# MCU.net
KiCad netlist of a schematic drawn in Altium Designer
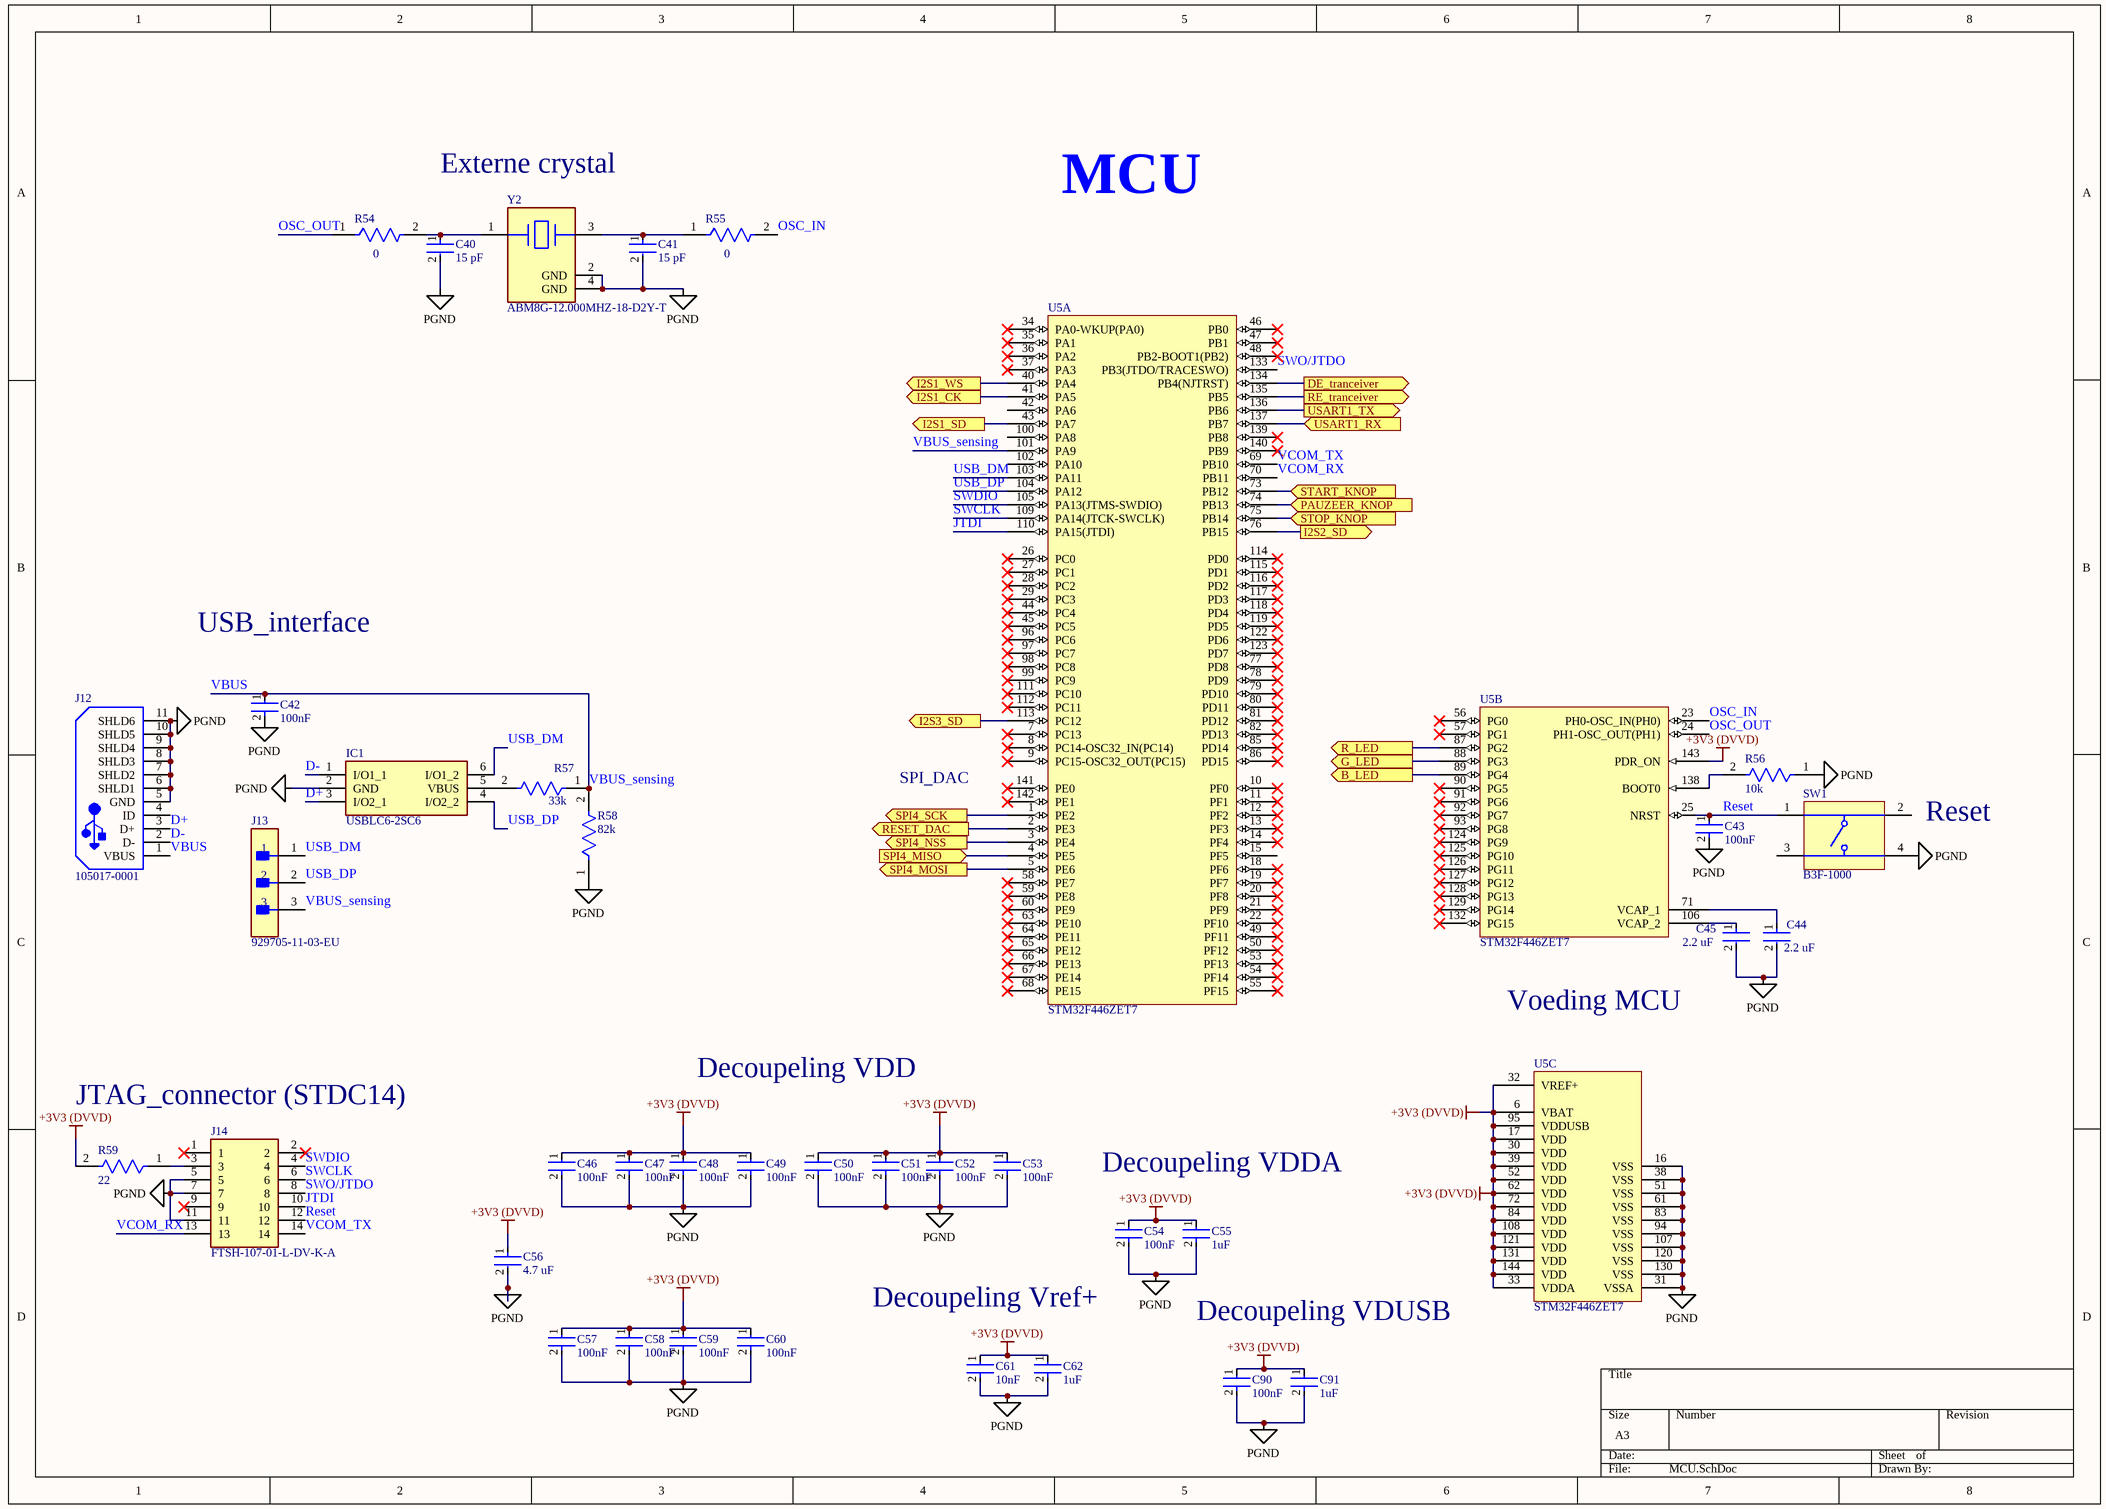
[diagram p0: MCU.SchDoc]

(export (version "E")
  (design (tool "Eeschema 10.0.6"))
  (components
    (comp (ref "C40")
      (value "15 pF")
      (footprint "FP-AC0603-MFG")
      (description "AC0603 15 pF NP0 5.00% 50 V")
      (fields
        (field (name "TOLERANCE") "0.05")
        (field (name "OCTOPART") "https://octopart.com/ac0603jrnpo9bn271-yageo-87214073")
      )
      (libsource (lib "Altium Content Vault") (part "11868f565c42a9108669ba33697ecf6"))
    )
    (comp (ref "C41")
      (value "15 pF")
      (footprint "FP-AC0603-MFG")
      (description "AC0603 15 pF NP0 5.00% 50 V")
      (fields
        (field (name "TOLERANCE") "0.05")
        (field (name "OCTOPART") "https://octopart.com/ac0603jrnpo9bn271-yageo-87214073")
      )
      (libsource (lib "Altium Content Vault") (part "11868f565c42a9108669ba33697ecf6"))
    )
    (comp (ref "C42")
      (value "100nF")
      (footprint "FP-GRM15-MFG")
      (description "CAP CER 0.1UF 16V X7R 0402")
      (fields (field (name "MANUFACTURER PART NUMBER") "GRM155R71C104KA88D") (field (name "TOLERANCE") "10%"))
      (libsource (lib "Altium Content Vault") (part "236180d848d6139a670b325ea6854c9"))
    )
    (comp (ref "C43")
      (value "100nF")
      (footprint "FP-GRM15-MFG")
      (description "CAP CER 0.1UF 16V X7R 0402")
      (fields (field (name "MANUFACTURER PART NUMBER") "GRM155R71C104KA88D") (field (name "TOLERANCE") "10%"))
      (libsource (lib "Altium Content Vault") (part "236180d848d6139a670b325ea6854c9"))
    )
    (comp (ref "C44")
      (value "2.2 uF")
      (footprint "FP-C0603C-CF-MFG")
      (description "CAP CER 2.2 UF 50V 5% X7R 0603")
      (fields (field (name "TOLERANCE") "0.05") (field (name "MANUFACTURER PART NUMBER") "C0603C104J5RACTU"))
      (libsource (lib "Altium Content Vault") (part "b4654b650e69147ec39a6b967a45e02"))
    )
    (comp (ref "C45")
      (value "2.2 uF")
      (footprint "FP-C0603C-CF-MFG")
      (description "CAP CER 2.2 UF 50V 5% X7R 0603")
      (fields (field (name "TOLERANCE") "0.05") (field (name "MANUFACTURER PART NUMBER") "C0603C104J5RACTU"))
      (libsource (lib "Altium Content Vault") (part "b4654b650e69147ec39a6b967a45e02"))
    )
    (comp (ref "C46")
      (value "100nF")
      (footprint "FP-GRM15-MFG")
      (description "CAP CER 0.1UF 16V X7R 0402")
      (fields (field (name "MANUFACTURER PART NUMBER") "GRM155R71C104KA88D") (field (name "TOLERANCE") "10%"))
      (libsource (lib "Altium Content Vault") (part "236180d848d6139a670b325ea6854c9"))
    )
    (comp (ref "C47")
      (value "100nF")
      (footprint "FP-GRM15-MFG")
      (description "CAP CER 0.1UF 16V X7R 0402")
      (fields (field (name "MANUFACTURER PART NUMBER") "GRM155R71C104KA88D") (field (name "TOLERANCE") "10%"))
      (libsource (lib "Altium Content Vault") (part "236180d848d6139a670b325ea6854c9"))
    )
    (comp (ref "C48")
      (value "100nF")
      (footprint "FP-GRM15-MFG")
      (description "CAP CER 0.1UF 16V X7R 0402")
      (fields (field (name "MANUFACTURER PART NUMBER") "GRM155R71C104KA88D") (field (name "TOLERANCE") "10%"))
      (libsource (lib "Altium Content Vault") (part "236180d848d6139a670b325ea6854c9"))
    )
    (comp (ref "C49")
      (value "100nF")
      (footprint "FP-GRM15-MFG")
      (description "CAP CER 0.1UF 16V X7R 0402")
      (fields (field (name "MANUFACTURER PART NUMBER") "GRM155R71C104KA88D") (field (name "TOLERANCE") "10%"))
      (libsource (lib "Altium Content Vault") (part "236180d848d6139a670b325ea6854c9"))
    )
    (comp (ref "C50")
      (value "100nF")
      (footprint "FP-GRM15-MFG")
      (description "CAP CER 0.1UF 16V X7R 0402")
      (fields (field (name "MANUFACTURER PART NUMBER") "GRM155R71C104KA88D") (field (name "TOLERANCE") "10%"))
      (libsource (lib "Altium Content Vault") (part "236180d848d6139a670b325ea6854c9"))
    )
    (comp (ref "C51")
      (value "100nF")
      (footprint "FP-GRM15-MFG")
      (description "CAP CER 0.1UF 16V X7R 0402")
      (fields (field (name "MANUFACTURER PART NUMBER") "GRM155R71C104KA88D") (field (name "TOLERANCE") "10%"))
      (libsource (lib "Altium Content Vault") (part "236180d848d6139a670b325ea6854c9"))
    )
    (comp (ref "C52")
      (value "100nF")
      (footprint "FP-GRM15-MFG")
      (description "CAP CER 0.1UF 16V X7R 0402")
      (fields (field (name "MANUFACTURER PART NUMBER") "GRM155R71C104KA88D") (field (name "TOLERANCE") "10%"))
      (libsource (lib "Altium Content Vault") (part "236180d848d6139a670b325ea6854c9"))
    )
    (comp (ref "C53")
      (value "100nF")
      (footprint "FP-GRM15-MFG")
      (description "CAP CER 0.1UF 16V X7R 0402")
      (fields (field (name "MANUFACTURER PART NUMBER") "GRM155R71C104KA88D") (field (name "TOLERANCE") "10%"))
      (libsource (lib "Altium Content Vault") (part "236180d848d6139a670b325ea6854c9"))
    )
    (comp (ref "C54")
      (value "100nF")
      (footprint "FP-GRM15-MFG")
      (description "CAP CER 0.1UF 16V X7R 0402")
      (fields (field (name "MANUFACTURER PART NUMBER") "GRM155R71C104KA88D") (field (name "TOLERANCE") "10%"))
      (libsource (lib "Altium Content Vault") (part "236180d848d6139a670b325ea6854c9"))
    )
    (comp (ref "C55")
      (value "1uF")
      (footprint "FP-GRM15-MFG")
      (description "CAP CER 1UF 16V X7R 0402")
      (fields (field (name "MANUFACTURER PART NUMBER") "GRM155R71C104KA88D") (field (name "TOLERANCE") "10%"))
      (libsource (lib "Altium Content Vault") (part "236180d848d6139a670b325ea6854c9"))
    )
    (comp (ref "C56")
      (value "4.7 uF")
      (footprint "FP-C0603C-CF-MFG")
      (description "CAP CER 4.7 UF 50V 5% X7R 0603")
      (fields (field (name "TOLERANCE") "0.05") (field (name "MANUFACTURER PART NUMBER") "C0603C104J5RACTU"))
      (libsource (lib "Altium Content Vault") (part "b4654b650e69147ec39a6b967a45e02"))
    )
    (comp (ref "C57")
      (value "100nF")
      (footprint "FP-GRM15-MFG")
      (description "CAP CER 0.1UF 16V X7R 0402")
      (fields (field (name "MANUFACTURER PART NUMBER") "GRM155R71C104KA88D") (field (name "TOLERANCE") "10%"))
      (libsource (lib "Altium Content Vault") (part "236180d848d6139a670b325ea6854c9"))
    )
    (comp (ref "C58")
      (value "100nF")
      (footprint "FP-GRM15-MFG")
      (description "CAP CER 0.1UF 16V X7R 0402")
      (fields (field (name "MANUFACTURER PART NUMBER") "GRM155R71C104KA88D") (field (name "TOLERANCE") "10%"))
      (libsource (lib "Altium Content Vault") (part "236180d848d6139a670b325ea6854c9"))
    )
    (comp (ref "C59")
      (value "100nF")
      (footprint "FP-GRM15-MFG")
      (description "CAP CER 0.1UF 16V X7R 0402")
      (fields (field (name "MANUFACTURER PART NUMBER") "GRM155R71C104KA88D") (field (name "TOLERANCE") "10%"))
      (libsource (lib "Altium Content Vault") (part "236180d848d6139a670b325ea6854c9"))
    )
    (comp (ref "C60")
      (value "100nF")
      (footprint "FP-GRM15-MFG")
      (description "CAP CER 0.1UF 16V X7R 0402")
      (fields (field (name "MANUFACTURER PART NUMBER") "GRM155R71C104KA88D") (field (name "TOLERANCE") "10%"))
      (libsource (lib "Altium Content Vault") (part "236180d848d6139a670b325ea6854c9"))
    )
    (comp (ref "C61")
      (value "10nF")
      (footprint "FP-GRM15-MFG")
      (description "CAP CER 10nF 16V X7R 0402")
      (fields (field (name "MANUFACTURER PART NUMBER") "GRM155R71C104KA88D") (field (name "TOLERANCE") "10%"))
      (libsource (lib "Altium Content Vault") (part "236180d848d6139a670b325ea6854c9"))
    )
    (comp (ref "C62")
      (value "1uF")
      (footprint "FP-GRM15-MFG")
      (description "CAP CER 1UF 16V X7R 0402")
      (fields (field (name "MANUFACTURER PART NUMBER") "GRM155R71C104KA88D") (field (name "TOLERANCE") "10%"))
      (libsource (lib "Altium Content Vault") (part "236180d848d6139a670b325ea6854c9"))
    )
    (comp (ref "C90")
      (value "100nF")
      (footprint "FP-GRM15-MFG")
      (description "CAP CER 0.1UF 16V X7R 0402")
      (fields (field (name "MANUFACTURER PART NUMBER") "GRM155R71C104KA88D") (field (name "TOLERANCE") "10%"))
      (libsource (lib "Altium Content Vault") (part "236180d848d6139a670b325ea6854c9"))
    )
    (comp (ref "C91")
      (value "1uF")
      (footprint "FP-GRM15-MFG")
      (description "CAP CER 1UF 16V X7R 0402")
      (fields (field (name "MANUFACTURER PART NUMBER") "GRM155R71C104KA88D") (field (name "TOLERANCE") "10%"))
      (libsource (lib "Altium Content Vault") (part "236180d848d6139a670b325ea6854c9"))
    )
    (comp (ref "IC1")
      (value "USBLC6-2SC6")
      (footprint "SamacSys:SOT95P280X145-6N")
      (description "ESD-onderdrukkers/TVS-diodes ESD Protection Low Cap")
      (fields (field (name "MOUSER PART NUMBER") "511-USBLC6-2SC6"))
      (libsource (lib "*") (part "USBLC6-2SC6"))
    )
    (comp (ref "J12")
      (value "105017-0001")
      (footprint "USB-MICRO-B_V")
      (fields (field (name "MANUFACTURER") "Molex"))
      (libsource (lib "Altium Content Vault") (part "USB-5-6SHLD"))
    )
    (comp (ref "J13")
      (value "929705-11-03-EU")
      (footprint "FP-929705-11-03-EU-MFG")
      (description "CONN HEADER VERT 3POS 2.54MM\r\nEuro circruits generic component:\r\nGPHA-1X03")
      (fields (field (name "EUROCIRCUITS_GENERIC_PART_NUMBER") "GPHA-1X03"))
      (libsource (lib "Altium Content Vault") (part "0d3f023dd272f625e17a2be33dea85f"))
    )
    (comp (ref "J14")
      (value "FTSH-107-01-L-DV-K-A")
      (footprint "SamacSys:FTSH-107-XX-YYY-DV-K-A")
      (fields (field (name "MOUSER PART NUMBER") "200-FTSH10701LDVKA"))
      (libsource (lib "*") (part "FTSH-107-01-L-DV-K-A"))
    )
    (comp (ref "R54")
      (value "0")
      (footprint "FP-CRCW1206-MFG")
      (description "CRCW12060000ZSTA Zero Ohm Resistor, Jumper, 1206 [3216 Metric], Thick Film, 250 mW, Surface Mount")
      (libsource (lib "Altium Content Vault") (part "1029c3af85768c4190bb7ad29bc67b5"))
    )
    (comp (ref "R55")
      (value "0")
      (footprint "FP-CRCW1206-MFG")
      (description "CRCW12060000ZSTA Zero Ohm Resistor, Jumper, 1206 [3216 Metric], Thick Film, 250 mW, Surface Mount")
      (libsource (lib "Altium Content Vault") (part "1029c3af85768c4190bb7ad29bc67b5"))
    )
    (comp (ref "R56")
      (value "10k")
      (footprint "FP-RC1608-IPC_B")
      (fields (field (name "TOLERANCE") "1%"))
      (libsource (lib "Altium Content Vault") (part "1029c3af85768c4190bb7ad29bc67b5"))
    )
    (comp (ref "R57")
      (value "33k")
      (footprint "FP-RC1608-IPC_B")
      (fields (field (name "TOLERANCE") "1%"))
      (libsource (lib "Altium Content Vault") (part "1029c3af85768c4190bb7ad29bc67b5"))
    )
    (comp (ref "R58")
      (value "82k")
      (footprint "FP-RC1608-IPC_B")
      (fields (field (name "TOLERANCE") "1%"))
      (libsource (lib "Altium Content Vault") (part "1029c3af85768c4190bb7ad29bc67b5"))
    )
    (comp (ref "R59")
      (value "22")
      (footprint "FP-RC1608-IPC_B")
      (fields (field (name "TOLERANCE") "1%"))
      (libsource (lib "Altium Content Vault") (part "1029c3af85768c4190bb7ad29bc67b5"))
    )
    (comp (ref "SW1")
      (value "B3F-1000")
      (footprint "OMRON-B3F-1000-4_V")
      (description "Tactile Switch, SPST-NO, 0.05 A, 5 to 24 V, -25 to 70 degC, 4-Pin THD, RoHS, Bulk")
      (libsource (lib "Altium Content Vault") (part "SW-SPST-4_A"))
    )
    (comp (ref "U5")
      (value "STM32F446ZET7")
      (footprint "STM-LQFP144_M")
      (libsource (lib "Altium Content Vault") (part "MC-ARM-STM32F446-LQFP144"))
    )
    (comp (ref "Y2")
      (value "ABM8G-12.000MHZ-18-D2Y-T")
      (footprint "FP-ABM8G-MFG")
      (description "Crystal 12MHz ±20ppm (Tol) ±30ppm (Stability) 18pF FUND 120Ω 4-Pin SMD T/R")
      (fields (field (name "TOLERANCE") "20ppm"))
      (libsource (lib "Altium Content Vault") (part "48e526d86b7f2615d98721063c72f49"))
    )
  )
  (nets
    (net (code "1") (name "+3V3 (DVVD)") (class "Default")
      (node (ref "C46") (pin "1") (pinfunction "1_1") (pintype "passive"))
      (node (ref "C47") (pin "1") (pinfunction "1_1") (pintype "passive"))
      (node (ref "C48") (pin "1") (pinfunction "1_1") (pintype "passive"))
      (node (ref "C49") (pin "1") (pinfunction "1_1") (pintype "passive"))
      (node (ref "C50") (pin "1") (pinfunction "1_1") (pintype "passive"))
      (node (ref "C51") (pin "1") (pinfunction "1_1") (pintype "passive"))
      (node (ref "C52") (pin "1") (pinfunction "1_1") (pintype "passive"))
      (node (ref "C53") (pin "1") (pinfunction "1_1") (pintype "passive"))
      (node (ref "C54") (pin "1") (pinfunction "1_1") (pintype "passive"))
      (node (ref "C55") (pin "1") (pinfunction "1_1") (pintype "passive"))
      (node (ref "C56") (pin "1") (pinfunction "1_1") (pintype "passive"))
      (node (ref "C57") (pin "1") (pinfunction "1_1") (pintype "passive"))
      (node (ref "C58") (pin "1") (pinfunction "1_1") (pintype "passive"))
      (node (ref "C59") (pin "1") (pinfunction "1_1") (pintype "passive"))
      (node (ref "C60") (pin "1") (pinfunction "1_1") (pintype "passive"))
      (node (ref "C61") (pin "1") (pinfunction "1_1") (pintype "passive"))
      (node (ref "C62") (pin "1") (pinfunction "1_1") (pintype "passive"))
      (node (ref "C90") (pin "1") (pinfunction "1_1") (pintype "passive"))
      (node (ref "C91") (pin "1") (pinfunction "1_1") (pintype "passive"))
      (node (ref "R59") (pin "2") (pinfunction "2_2") (pintype "passive"))
      (node (ref "U5") (pin "108") (pinfunction "VDD_108") (pintype "power_in"))
      (node (ref "U5") (pin "121") (pinfunction "VDD_121") (pintype "power_in"))
      (node (ref "U5") (pin "131") (pinfunction "VDD_131") (pintype "power_in"))
      (node (ref "U5") (pin "143") (pinfunction "PDR_ON_143") (pintype "input"))
      (node (ref "U5") (pin "144") (pinfunction "VDD_144") (pintype "power_in"))
      (node (ref "U5") (pin "17") (pinfunction "VDD_17") (pintype "power_in"))
      (node (ref "U5") (pin "30") (pinfunction "VDD_30") (pintype "power_in"))
      (node (ref "U5") (pin "32") (pinfunction "VREF+_32") (pintype "power_in"))
      (node (ref "U5") (pin "33") (pinfunction "VDDA_33") (pintype "power_in"))
      (node (ref "U5") (pin "39") (pinfunction "VDD_39") (pintype "power_in"))
      (node (ref "U5") (pin "52") (pinfunction "VDD_52") (pintype "power_in"))
      (node (ref "U5") (pin "6") (pinfunction "VBAT_6") (pintype "power_in"))
      (node (ref "U5") (pin "62") (pinfunction "VDD_62") (pintype "power_in"))
      (node (ref "U5") (pin "72") (pinfunction "VDD_72") (pintype "power_in"))
      (node (ref "U5") (pin "84") (pinfunction "VDD_84") (pintype "power_in"))
      (node (ref "U5") (pin "95") (pinfunction "VDDUSB_95") (pintype "power_in"))
    )
    (net (code "3") (name "/B_LED") (class "Default")
      (node (ref "U5") (pin "89") (pinfunction "PG4_89") (pintype "bidirectional"))
    )
    (net (code "4") (name "/D+") (class "Default")
      (node (ref "IC1") (pin "3") (pinfunction "I/O2_1_3") (pintype "passive"))
      (node (ref "J12") (pin "3") (pinfunction "D+_3") (pintype "passive"))
    )
    (net (code "5") (name "/D-") (class "Default")
      (node (ref "IC1") (pin "1") (pinfunction "I/O1_1_1") (pintype "passive"))
      (node (ref "J12") (pin "2") (pinfunction "D-_2") (pintype "passive"))
    )
    (net (code "6") (name "/DE_tranceiver") (class "Default")
      (node (ref "U5") (pin "134") (pinfunction "PB4(NJTRST)_134") (pintype "bidirectional"))
    )
    (net (code "7") (name "/G_LED") (class "Default")
      (node (ref "U5") (pin "88") (pinfunction "PG3_88") (pintype "bidirectional"))
    )
    (net (code "8") (name "/I2S1_CK") (class "Default")
      (node (ref "U5") (pin "41") (pinfunction "PA5_41") (pintype "bidirectional"))
    )
    (net (code "9") (name "/I2S1_SD") (class "Default")
      (node (ref "U5") (pin "43") (pinfunction "PA7_43") (pintype "bidirectional"))
    )
    (net (code "10") (name "/I2S1_WS") (class "Default")
      (node (ref "U5") (pin "40") (pinfunction "PA4_40") (pintype "bidirectional"))
    )
    (net (code "11") (name "/I2S2_SD") (class "Default")
      (node (ref "U5") (pin "76") (pinfunction "PB15_76") (pintype "bidirectional"))
    )
    (net (code "12") (name "/I2S3_SD") (class "Default")
      (node (ref "U5") (pin "113") (pinfunction "PC12_113") (pintype "bidirectional"))
    )
    (net (code "13") (name "/JTDI") (class "Default")
      (node (ref "J14") (pin "10") (pinfunction "10_10") (pintype "passive"))
      (node (ref "U5") (pin "110") (pinfunction "PA15(JTDI)_110") (pintype "bidirectional"))
    )
    (net (code "14") (name "/OSC_IN") (class "Default")
      (node (ref "R55") (pin "2") (pinfunction "2_2") (pintype "passive"))
      (node (ref "U5") (pin "23") (pinfunction "PH0-OSC_IN(PH0)_23") (pintype "bidirectional"))
    )
    (net (code "15") (name "/OSC_OUT") (class "Default")
      (node (ref "R54") (pin "1") (pinfunction "1_1") (pintype "passive"))
      (node (ref "U5") (pin "24") (pinfunction "PH1-OSC_OUT(PH1)_24") (pintype "bidirectional"))
    )
    (net (code "16") (name "/PAUZEER_KNOP") (class "Default")
      (node (ref "U5") (pin "74") (pinfunction "PB13_74") (pintype "bidirectional"))
    )
    (net (code "17") (name "/RESET_DAC") (class "Default")
      (node (ref "U5") (pin "2") (pinfunction "PE3_2") (pintype "bidirectional"))
    )
    (net (code "18") (name "/RE_tranceiver") (class "Default")
      (node (ref "U5") (pin "135") (pinfunction "PB5_135") (pintype "bidirectional"))
    )
    (net (code "19") (name "/R_LED") (class "Default")
      (node (ref "U5") (pin "87") (pinfunction "PG2_87") (pintype "bidirectional"))
    )
    (net (code "20") (name "/Reset") (class "Default")
      (node (ref "C43") (pin "1") (pinfunction "1_1") (pintype "passive"))
      (node (ref "J14") (pin "12") (pinfunction "12_12") (pintype "passive"))
      (node (ref "SW1") (pin "1") (pinfunction "1_1") (pintype "passive"))
      (node (ref "U5") (pin "25") (pinfunction "NRST_25") (pintype "bidirectional"))
    )
    (net (code "21") (name "/SPI4_MISO") (class "Default")
      (node (ref "U5") (pin "4") (pinfunction "PE5_4") (pintype "bidirectional"))
    )
    (net (code "22") (name "/SPI4_MOSI") (class "Default")
      (node (ref "U5") (pin "5") (pinfunction "PE6_5") (pintype "bidirectional"))
    )
    (net (code "23") (name "/SPI4_NSS") (class "Default")
      (node (ref "U5") (pin "3") (pinfunction "PE4_3") (pintype "bidirectional"))
    )
    (net (code "24") (name "/SPI4_SCK") (class "Default")
      (node (ref "U5") (pin "1") (pinfunction "PE2_1") (pintype "bidirectional"))
    )
    (net (code "25") (name "/START_KNOP") (class "Default")
      (node (ref "U5") (pin "73") (pinfunction "PB12_73") (pintype "bidirectional"))
    )
    (net (code "26") (name "/STOP_KNOP") (class "Default")
      (node (ref "U5") (pin "75") (pinfunction "PB14_75") (pintype "bidirectional"))
    )
    (net (code "27") (name "/SWCLK") (class "Default")
      (node (ref "J14") (pin "6") (pinfunction "6_6") (pintype "passive"))
      (node (ref "U5") (pin "109") (pinfunction "PA14(JTCK-SWCLK)_109") (pintype "bidirectional"))
    )
    (net (code "28") (name "/SWDIO") (class "Default")
      (node (ref "J14") (pin "4") (pinfunction "4_4") (pintype "passive"))
      (node (ref "U5") (pin "105") (pinfunction "PA13(JTMS-SWDIO)_105") (pintype "bidirectional"))
    )
    (net (code "29") (name "/SWO{slash}JTDO") (class "Default")
      (node (ref "J14") (pin "8") (pinfunction "8_8") (pintype "passive"))
      (node (ref "U5") (pin "133") (pinfunction "PB3(JTDO/TRACESWO)_133") (pintype "bidirectional"))
    )
    (net (code "30") (name "/USART1_RX") (class "Default")
      (node (ref "U5") (pin "137") (pinfunction "PB7_137") (pintype "bidirectional"))
    )
    (net (code "31") (name "/USART1_TX") (class "Default")
      (node (ref "U5") (pin "136") (pinfunction "PB6_136") (pintype "bidirectional"))
    )
    (net (code "32") (name "/USB_DM") (class "Default")
      (node (ref "IC1") (pin "6") (pinfunction "I/O1_2_6") (pintype "passive"))
      (node (ref "J13") (pin "1") (pinfunction "1_1") (pintype "passive"))
      (node (ref "U5") (pin "103") (pinfunction "PA11_103") (pintype "bidirectional"))
    )
    (net (code "33") (name "/USB_DP") (class "Default")
      (node (ref "IC1") (pin "4") (pinfunction "I/O2_2_4") (pintype "passive"))
      (node (ref "J13") (pin "2") (pinfunction "2_2") (pintype "passive"))
      (node (ref "U5") (pin "104") (pinfunction "PA12_104") (pintype "bidirectional"))
    )
    (net (code "34") (name "/VBUS") (class "Default")
      (node (ref "C42") (pin "1") (pinfunction "1_1") (pintype "passive"))
      (node (ref "J12") (pin "1") (pinfunction "VBUS_1") (pintype "passive"))
      (node (ref "J13") (pin "3") (pinfunction "3_3") (pintype "passive"))
      (node (ref "R57") (pin "1") (pinfunction "1_1") (pintype "passive"))
      (node (ref "R58") (pin "2") (pinfunction "2_2") (pintype "passive"))
      (node (ref "U5") (pin "101") (pinfunction "PA9_101") (pintype "bidirectional"))
    )
    (net (code "35") (name "/VCOM_RX") (class "Default")
      (node (ref "J14") (pin "13") (pinfunction "13_13") (pintype "passive"))
      (node (ref "U5") (pin "70") (pinfunction "PB11_70") (pintype "bidirectional"))
    )
    (net (code "36") (name "/VCOM_TX") (class "Default")
      (node (ref "J14") (pin "14") (pinfunction "14_14") (pintype "passive"))
      (node (ref "U5") (pin "69") (pinfunction "PB10_69") (pintype "bidirectional"))
    )
    (net (code "37") (name "Net-(C40-Pad1)") (class "Default")
      (node (ref "C40") (pin "1") (pinfunction "1_1") (pintype "passive"))
      (node (ref "R54") (pin "2") (pinfunction "2_2") (pintype "passive"))
      (node (ref "Y2") (pin "1") (pinfunction "1_1") (pintype "passive"))
    )
    (net (code "38") (name "Net-(C41-Pad1)") (class "Default")
      (node (ref "C41") (pin "1") (pinfunction "1_1") (pintype "passive"))
      (node (ref "R55") (pin "1") (pinfunction "1_1") (pintype "passive"))
      (node (ref "Y2") (pin "3") (pinfunction "3_3") (pintype "passive"))
    )
    (net (code "39") (name "Net-(IC1-VBUS)") (class "Default")
      (node (ref "IC1") (pin "5") (pinfunction "VBUS_5") (pintype "passive"))
      (node (ref "R57") (pin "2") (pinfunction "2_2") (pintype "passive"))
    )
    (net (code "40") (name "Net-(J14-Pad3)") (class "Default")
      (node (ref "J14") (pin "3") (pinfunction "3_3") (pintype "passive"))
      (node (ref "R59") (pin "1") (pinfunction "1_1") (pintype "passive"))
    )
    (net (code "41") (name "Net-(U5B-BOOT0)") (class "Default")
      (node (ref "R56") (pin "2") (pinfunction "2_2") (pintype "passive"))
      (node (ref "U5") (pin "138") (pinfunction "BOOT0_138") (pintype "input"))
    )
    (net (code "42") (name "Net-(U5B-VCAP_1)") (class "Default")
      (node (ref "C44") (pin "1") (pinfunction "1_1") (pintype "passive"))
      (node (ref "U5") (pin "71") (pinfunction "VCAP_1_71") (pintype "passive"))
    )
    (net (code "43") (name "Net-(U5B-VCAP_2)") (class "Default")
      (node (ref "C45") (pin "1") (pinfunction "1_1") (pintype "passive"))
      (node (ref "U5") (pin "106") (pinfunction "VCAP_2_106") (pintype "passive"))
    )
    (net (code "44") (name "PGND") (class "Default")
      (node (ref "C40") (pin "2") (pinfunction "2_2") (pintype "passive"))
      (node (ref "C41") (pin "2") (pinfunction "2_2") (pintype "passive"))
      (node (ref "C42") (pin "2") (pinfunction "2_2") (pintype "passive"))
      (node (ref "C43") (pin "2") (pinfunction "2_2") (pintype "passive"))
      (node (ref "C44") (pin "2") (pinfunction "2_2") (pintype "passive"))
      (node (ref "C45") (pin "2") (pinfunction "2_2") (pintype "passive"))
      (node (ref "C46") (pin "2") (pinfunction "2_2") (pintype "passive"))
      (node (ref "C47") (pin "2") (pinfunction "2_2") (pintype "passive"))
      (node (ref "C48") (pin "2") (pinfunction "2_2") (pintype "passive"))
      (node (ref "C49") (pin "2") (pinfunction "2_2") (pintype "passive"))
      (node (ref "C50") (pin "2") (pinfunction "2_2") (pintype "passive"))
      (node (ref "C51") (pin "2") (pinfunction "2_2") (pintype "passive"))
      (node (ref "C52") (pin "2") (pinfunction "2_2") (pintype "passive"))
      (node (ref "C53") (pin "2") (pinfunction "2_2") (pintype "passive"))
      (node (ref "C54") (pin "2") (pinfunction "2_2") (pintype "passive"))
      (node (ref "C55") (pin "2") (pinfunction "2_2") (pintype "passive"))
      (node (ref "C56") (pin "2") (pinfunction "2_2") (pintype "passive"))
      (node (ref "C57") (pin "2") (pinfunction "2_2") (pintype "passive"))
      (node (ref "C58") (pin "2") (pinfunction "2_2") (pintype "passive"))
      (node (ref "C59") (pin "2") (pinfunction "2_2") (pintype "passive"))
      (node (ref "C60") (pin "2") (pinfunction "2_2") (pintype "passive"))
      (node (ref "C61") (pin "2") (pinfunction "2_2") (pintype "passive"))
      (node (ref "C62") (pin "2") (pinfunction "2_2") (pintype "passive"))
      (node (ref "C90") (pin "2") (pinfunction "2_2") (pintype "passive"))
      (node (ref "C91") (pin "2") (pinfunction "2_2") (pintype "passive"))
      (node (ref "IC1") (pin "2") (pinfunction "GND_2") (pintype "passive"))
      (node (ref "J12") (pin "10") (pinfunction "SHLD5_10") (pintype "passive"))
      (node (ref "J12") (pin "11") (pinfunction "SHLD6_11") (pintype "passive"))
      (node (ref "J12") (pin "5") (pinfunction "GND_5") (pintype "passive"))
      (node (ref "J12") (pin "6") (pinfunction "SHLD1_6") (pintype "passive"))
      (node (ref "J12") (pin "7") (pinfunction "SHLD2_7") (pintype "passive"))
      (node (ref "J12") (pin "8") (pinfunction "SHLD3_8") (pintype "passive"))
      (node (ref "J12") (pin "9") (pinfunction "SHLD4_9") (pintype "passive"))
      (node (ref "J14") (pin "11") (pinfunction "11_11") (pintype "passive"))
      (node (ref "J14") (pin "5") (pinfunction "5_5") (pintype "passive"))
      (node (ref "J14") (pin "7") (pinfunction "7_7") (pintype "passive"))
      (node (ref "R56") (pin "1") (pinfunction "1_1") (pintype "passive"))
      (node (ref "R58") (pin "1") (pinfunction "1_1") (pintype "passive"))
      (node (ref "SW1") (pin "4") (pinfunction "4_4") (pintype "passive"))
      (node (ref "U5") (pin "107") (pinfunction "VSS_107") (pintype "power_in"))
      (node (ref "U5") (pin "120") (pinfunction "VSS_120") (pintype "power_in"))
      (node (ref "U5") (pin "130") (pinfunction "VSS_130") (pintype "power_in"))
      (node (ref "U5") (pin "16") (pinfunction "VSS_16") (pintype "power_in"))
      (node (ref "U5") (pin "31") (pinfunction "VSSA_31") (pintype "power_in"))
      (node (ref "U5") (pin "38") (pinfunction "VSS_38") (pintype "power_in"))
      (node (ref "U5") (pin "51") (pinfunction "VSS_51") (pintype "power_in"))
      (node (ref "U5") (pin "61") (pinfunction "VSS_61") (pintype "power_in"))
      (node (ref "U5") (pin "83") (pinfunction "VSS_83") (pintype "power_in"))
      (node (ref "U5") (pin "94") (pinfunction "VSS_94") (pintype "power_in"))
      (node (ref "Y2") (pin "2") (pinfunction "GND_2") (pintype "power_in"))
      (node (ref "Y2") (pin "4") (pinfunction "GND_4") (pintype "power_in"))
    )
    (net (code "45") (name "unconnected-(J12-ID-Pad4)") (class "Default")
      (node (ref "J12") (pin "4") (pinfunction "ID_4") (pintype "passive"))
    )
    (net (code "46") (name "unconnected-(J14-Pad1)") (class "Default")
      (node (ref "J14") (pin "1") (pinfunction "1_1") (pintype "passive+no_connect"))
    )
    (net (code "47") (name "unconnected-(J14-Pad2)") (class "Default")
      (node (ref "J14") (pin "2") (pinfunction "2_2") (pintype "passive+no_connect"))
    )
    (net (code "48") (name "unconnected-(J14-Pad9)") (class "Default")
      (node (ref "J14") (pin "9") (pinfunction "9_9") (pintype "passive+no_connect"))
    )
    (net (code "49") (name "unconnected-(SW1-Pad2)") (class "Default")
      (node (ref "SW1") (pin "2") (pinfunction "2_2") (pintype "passive"))
    )
    (net (code "50") (name "unconnected-(SW1-Pad3)") (class "Default")
      (node (ref "SW1") (pin "3") (pinfunction "3_3") (pintype "passive"))
    )
    (net (code "51") (name "unconnected-(U5A-PA0-WKUP(PA0)-Pad34)") (class "Default")
      (node (ref "U5") (pin "34") (pinfunction "PA0-WKUP(PA0)_34") (pintype "bidirectional+no_connect"))
    )
    (net (code "52") (name "unconnected-(U5A-PA1-Pad35)") (class "Default")
      (node (ref "U5") (pin "35") (pinfunction "PA1_35") (pintype "bidirectional+no_connect"))
    )
    (net (code "53") (name "unconnected-(U5A-PA2-Pad36)") (class "Default")
      (node (ref "U5") (pin "36") (pinfunction "PA2_36") (pintype "bidirectional+no_connect"))
    )
    (net (code "54") (name "unconnected-(U5A-PA3-Pad37)") (class "Default")
      (node (ref "U5") (pin "37") (pinfunction "PA3_37") (pintype "bidirectional+no_connect"))
    )
    (net (code "55") (name "unconnected-(U5A-PA6-Pad42)") (class "Default")
      (node (ref "U5") (pin "42") (pinfunction "PA6_42") (pintype "bidirectional"))
    )
    (net (code "56") (name "unconnected-(U5A-PA8-Pad100)") (class "Default")
      (node (ref "U5") (pin "100") (pinfunction "PA8_100") (pintype "bidirectional"))
    )
    (net (code "57") (name "unconnected-(U5A-PA10-Pad102)") (class "Default")
      (node (ref "U5") (pin "102") (pinfunction "PA10_102") (pintype "bidirectional"))
    )
    (net (code "58") (name "unconnected-(U5A-PB0-Pad46)") (class "Default")
      (node (ref "U5") (pin "46") (pinfunction "PB0_46") (pintype "bidirectional+no_connect"))
    )
    (net (code "59") (name "unconnected-(U5A-PB1-Pad47)") (class "Default")
      (node (ref "U5") (pin "47") (pinfunction "PB1_47") (pintype "bidirectional+no_connect"))
    )
    (net (code "60") (name "unconnected-(U5A-PB2-BOOT1(PB2)-Pad48)") (class "Default")
      (node (ref "U5") (pin "48") (pinfunction "PB2-BOOT1(PB2)_48") (pintype "bidirectional+no_connect"))
    )
    (net (code "61") (name "unconnected-(U5A-PB8-Pad139)") (class "Default")
      (node (ref "U5") (pin "139") (pinfunction "PB8_139") (pintype "bidirectional+no_connect"))
    )
    (net (code "62") (name "unconnected-(U5A-PB9-Pad140)") (class "Default")
      (node (ref "U5") (pin "140") (pinfunction "PB9_140") (pintype "bidirectional+no_connect"))
    )
    (net (code "63") (name "unconnected-(U5A-PC0-Pad26)") (class "Default")
      (node (ref "U5") (pin "26") (pinfunction "PC0_26") (pintype "bidirectional+no_connect"))
    )
    (net (code "64") (name "unconnected-(U5A-PC1-Pad27)") (class "Default")
      (node (ref "U5") (pin "27") (pinfunction "PC1_27") (pintype "bidirectional+no_connect"))
    )
    (net (code "65") (name "unconnected-(U5A-PC2-Pad28)") (class "Default")
      (node (ref "U5") (pin "28") (pinfunction "PC2_28") (pintype "bidirectional+no_connect"))
    )
    (net (code "66") (name "unconnected-(U5A-PC3-Pad29)") (class "Default")
      (node (ref "U5") (pin "29") (pinfunction "PC3_29") (pintype "bidirectional+no_connect"))
    )
    (net (code "67") (name "unconnected-(U5A-PC4-Pad44)") (class "Default")
      (node (ref "U5") (pin "44") (pinfunction "PC4_44") (pintype "bidirectional+no_connect"))
    )
    (net (code "68") (name "unconnected-(U5A-PC5-Pad45)") (class "Default")
      (node (ref "U5") (pin "45") (pinfunction "PC5_45") (pintype "bidirectional+no_connect"))
    )
    (net (code "69") (name "unconnected-(U5A-PC6-Pad96)") (class "Default")
      (node (ref "U5") (pin "96") (pinfunction "PC6_96") (pintype "bidirectional+no_connect"))
    )
    (net (code "70") (name "unconnected-(U5A-PC7-Pad97)") (class "Default")
      (node (ref "U5") (pin "97") (pinfunction "PC7_97") (pintype "bidirectional+no_connect"))
    )
    (net (code "71") (name "unconnected-(U5A-PC8-Pad98)") (class "Default")
      (node (ref "U5") (pin "98") (pinfunction "PC8_98") (pintype "bidirectional+no_connect"))
    )
    (net (code "72") (name "unconnected-(U5A-PC9-Pad99)") (class "Default")
      (node (ref "U5") (pin "99") (pinfunction "PC9_99") (pintype "bidirectional+no_connect"))
    )
    (net (code "73") (name "unconnected-(U5A-PC10-Pad111)") (class "Default")
      (node (ref "U5") (pin "111") (pinfunction "PC10_111") (pintype "bidirectional+no_connect"))
    )
    (net (code "74") (name "unconnected-(U5A-PC11-Pad112)") (class "Default")
      (node (ref "U5") (pin "112") (pinfunction "PC11_112") (pintype "bidirectional+no_connect"))
    )
    (net (code "75") (name "unconnected-(U5A-PC13-Pad7)") (class "Default")
      (node (ref "U5") (pin "7") (pinfunction "PC13_7") (pintype "bidirectional+no_connect"))
    )
    (net (code "76") (name "unconnected-(U5A-PC14-OSC32_IN(PC14)-Pad8)") (class "Default")
      (node (ref "U5") (pin "8") (pinfunction "PC14-OSC32_IN(PC14)_8") (pintype "bidirectional+no_connect"))
    )
    (net (code "77") (name "unconnected-(U5A-PC15-OSC32_OUT(PC15)-Pad9)") (class "Default")
      (node (ref "U5") (pin "9") (pinfunction "PC15-OSC32_OUT(PC15)_9") (pintype "bidirectional+no_connect"))
    )
    (net (code "78") (name "unconnected-(U5A-PD0-Pad114)") (class "Default")
      (node (ref "U5") (pin "114") (pinfunction "PD0_114") (pintype "bidirectional+no_connect"))
    )
    (net (code "79") (name "unconnected-(U5A-PD1-Pad115)") (class "Default")
      (node (ref "U5") (pin "115") (pinfunction "PD1_115") (pintype "bidirectional+no_connect"))
    )
    (net (code "80") (name "unconnected-(U5A-PD2-Pad116)") (class "Default")
      (node (ref "U5") (pin "116") (pinfunction "PD2_116") (pintype "bidirectional+no_connect"))
    )
    (net (code "81") (name "unconnected-(U5A-PD3-Pad117)") (class "Default")
      (node (ref "U5") (pin "117") (pinfunction "PD3_117") (pintype "bidirectional+no_connect"))
    )
    (net (code "82") (name "unconnected-(U5A-PD4-Pad118)") (class "Default")
      (node (ref "U5") (pin "118") (pinfunction "PD4_118") (pintype "bidirectional+no_connect"))
    )
    (net (code "83") (name "unconnected-(U5A-PD5-Pad119)") (class "Default")
      (node (ref "U5") (pin "119") (pinfunction "PD5_119") (pintype "bidirectional+no_connect"))
    )
    (net (code "84") (name "unconnected-(U5A-PD6-Pad122)") (class "Default")
      (node (ref "U5") (pin "122") (pinfunction "PD6_122") (pintype "bidirectional+no_connect"))
    )
    (net (code "85") (name "unconnected-(U5A-PD7-Pad123)") (class "Default")
      (node (ref "U5") (pin "123") (pinfunction "PD7_123") (pintype "bidirectional+no_connect"))
    )
    (net (code "86") (name "unconnected-(U5A-PD8-Pad77)") (class "Default")
      (node (ref "U5") (pin "77") (pinfunction "PD8_77") (pintype "bidirectional+no_connect"))
    )
    (net (code "87") (name "unconnected-(U5A-PD9-Pad78)") (class "Default")
      (node (ref "U5") (pin "78") (pinfunction "PD9_78") (pintype "bidirectional+no_connect"))
    )
    (net (code "88") (name "unconnected-(U5A-PD10-Pad79)") (class "Default")
      (node (ref "U5") (pin "79") (pinfunction "PD10_79") (pintype "bidirectional+no_connect"))
    )
    (net (code "89") (name "unconnected-(U5A-PD11-Pad80)") (class "Default")
      (node (ref "U5") (pin "80") (pinfunction "PD11_80") (pintype "bidirectional+no_connect"))
    )
    (net (code "90") (name "unconnected-(U5A-PD12-Pad81)") (class "Default")
      (node (ref "U5") (pin "81") (pinfunction "PD12_81") (pintype "bidirectional+no_connect"))
    )
    (net (code "91") (name "unconnected-(U5A-PD13-Pad82)") (class "Default")
      (node (ref "U5") (pin "82") (pinfunction "PD13_82") (pintype "bidirectional+no_connect"))
    )
    (net (code "92") (name "unconnected-(U5A-PD14-Pad85)") (class "Default")
      (node (ref "U5") (pin "85") (pinfunction "PD14_85") (pintype "bidirectional+no_connect"))
    )
    (net (code "93") (name "unconnected-(U5A-PD15-Pad86)") (class "Default")
      (node (ref "U5") (pin "86") (pinfunction "PD15_86") (pintype "bidirectional+no_connect"))
    )
    (net (code "94") (name "unconnected-(U5A-PE0-Pad141)") (class "Default")
      (node (ref "U5") (pin "141") (pinfunction "PE0_141") (pintype "bidirectional+no_connect"))
    )
    (net (code "95") (name "unconnected-(U5A-PE1-Pad142)") (class "Default")
      (node (ref "U5") (pin "142") (pinfunction "PE1_142") (pintype "bidirectional+no_connect"))
    )
    (net (code "96") (name "unconnected-(U5A-PE7-Pad58)") (class "Default")
      (node (ref "U5") (pin "58") (pinfunction "PE7_58") (pintype "bidirectional+no_connect"))
    )
    (net (code "97") (name "unconnected-(U5A-PE8-Pad59)") (class "Default")
      (node (ref "U5") (pin "59") (pinfunction "PE8_59") (pintype "bidirectional+no_connect"))
    )
    (net (code "98") (name "unconnected-(U5A-PE9-Pad60)") (class "Default")
      (node (ref "U5") (pin "60") (pinfunction "PE9_60") (pintype "bidirectional+no_connect"))
    )
    (net (code "99") (name "unconnected-(U5A-PE10-Pad63)") (class "Default")
      (node (ref "U5") (pin "63") (pinfunction "PE10_63") (pintype "bidirectional+no_connect"))
    )
    (net (code "100") (name "unconnected-(U5A-PE11-Pad64)") (class "Default")
      (node (ref "U5") (pin "64") (pinfunction "PE11_64") (pintype "bidirectional+no_connect"))
    )
    (net (code "101") (name "unconnected-(U5A-PE12-Pad65)") (class "Default")
      (node (ref "U5") (pin "65") (pinfunction "PE12_65") (pintype "bidirectional+no_connect"))
    )
    (net (code "102") (name "unconnected-(U5A-PE13-Pad66)") (class "Default")
      (node (ref "U5") (pin "66") (pinfunction "PE13_66") (pintype "bidirectional+no_connect"))
    )
    (net (code "103") (name "unconnected-(U5A-PE14-Pad67)") (class "Default")
      (node (ref "U5") (pin "67") (pinfunction "PE14_67") (pintype "bidirectional+no_connect"))
    )
    (net (code "104") (name "unconnected-(U5A-PE15-Pad68)") (class "Default")
      (node (ref "U5") (pin "68") (pinfunction "PE15_68") (pintype "bidirectional+no_connect"))
    )
    (net (code "105") (name "unconnected-(U5A-PF0-Pad10)") (class "Default")
      (node (ref "U5") (pin "10") (pinfunction "PF0_10") (pintype "bidirectional+no_connect"))
    )
    (net (code "106") (name "unconnected-(U5A-PF1-Pad11)") (class "Default")
      (node (ref "U5") (pin "11") (pinfunction "PF1_11") (pintype "bidirectional+no_connect"))
    )
    (net (code "107") (name "unconnected-(U5A-PF2-Pad12)") (class "Default")
      (node (ref "U5") (pin "12") (pinfunction "PF2_12") (pintype "bidirectional+no_connect"))
    )
    (net (code "108") (name "unconnected-(U5A-PF3-Pad13)") (class "Default")
      (node (ref "U5") (pin "13") (pinfunction "PF3_13") (pintype "bidirectional+no_connect"))
    )
    (net (code "109") (name "unconnected-(U5A-PF4-Pad14)") (class "Default")
      (node (ref "U5") (pin "14") (pinfunction "PF4_14") (pintype "bidirectional+no_connect"))
    )
    (net (code "110") (name "unconnected-(U5A-PF5-Pad15)") (class "Default")
      (node (ref "U5") (pin "15") (pinfunction "PF5_15") (pintype "bidirectional"))
    )
    (net (code "111") (name "unconnected-(U5A-PF6-Pad18)") (class "Default")
      (node (ref "U5") (pin "18") (pinfunction "PF6_18") (pintype "bidirectional+no_connect"))
    )
    (net (code "112") (name "unconnected-(U5A-PF7-Pad19)") (class "Default")
      (node (ref "U5") (pin "19") (pinfunction "PF7_19") (pintype "bidirectional+no_connect"))
    )
    (net (code "113") (name "unconnected-(U5A-PF8-Pad20)") (class "Default")
      (node (ref "U5") (pin "20") (pinfunction "PF8_20") (pintype "bidirectional+no_connect"))
    )
    (net (code "114") (name "unconnected-(U5A-PF9-Pad21)") (class "Default")
      (node (ref "U5") (pin "21") (pinfunction "PF9_21") (pintype "bidirectional+no_connect"))
    )
    (net (code "115") (name "unconnected-(U5A-PF10-Pad22)") (class "Default")
      (node (ref "U5") (pin "22") (pinfunction "PF10_22") (pintype "bidirectional+no_connect"))
    )
    (net (code "116") (name "unconnected-(U5A-PF11-Pad49)") (class "Default")
      (node (ref "U5") (pin "49") (pinfunction "PF11_49") (pintype "bidirectional+no_connect"))
    )
    (net (code "117") (name "unconnected-(U5A-PF12-Pad50)") (class "Default")
      (node (ref "U5") (pin "50") (pinfunction "PF12_50") (pintype "bidirectional+no_connect"))
    )
    (net (code "118") (name "unconnected-(U5A-PF13-Pad53)") (class "Default")
      (node (ref "U5") (pin "53") (pinfunction "PF13_53") (pintype "bidirectional+no_connect"))
    )
    (net (code "119") (name "unconnected-(U5A-PF14-Pad54)") (class "Default")
      (node (ref "U5") (pin "54") (pinfunction "PF14_54") (pintype "bidirectional+no_connect"))
    )
    (net (code "120") (name "unconnected-(U5A-PF15-Pad55)") (class "Default")
      (node (ref "U5") (pin "55") (pinfunction "PF15_55") (pintype "bidirectional+no_connect"))
    )
    (net (code "121") (name "unconnected-(U5B-PG0-Pad56)") (class "Default")
      (node (ref "U5") (pin "56") (pinfunction "PG0_56") (pintype "bidirectional+no_connect"))
    )
    (net (code "122") (name "unconnected-(U5B-PG1-Pad57)") (class "Default")
      (node (ref "U5") (pin "57") (pinfunction "PG1_57") (pintype "bidirectional+no_connect"))
    )
    (net (code "123") (name "unconnected-(U5B-PG5-Pad90)") (class "Default")
      (node (ref "U5") (pin "90") (pinfunction "PG5_90") (pintype "bidirectional+no_connect"))
    )
    (net (code "124") (name "unconnected-(U5B-PG6-Pad91)") (class "Default")
      (node (ref "U5") (pin "91") (pinfunction "PG6_91") (pintype "bidirectional+no_connect"))
    )
    (net (code "125") (name "unconnected-(U5B-PG7-Pad92)") (class "Default")
      (node (ref "U5") (pin "92") (pinfunction "PG7_92") (pintype "bidirectional+no_connect"))
    )
    (net (code "126") (name "unconnected-(U5B-PG8-Pad93)") (class "Default")
      (node (ref "U5") (pin "93") (pinfunction "PG8_93") (pintype "bidirectional+no_connect"))
    )
    (net (code "127") (name "unconnected-(U5B-PG9-Pad124)") (class "Default")
      (node (ref "U5") (pin "124") (pinfunction "PG9_124") (pintype "bidirectional+no_connect"))
    )
    (net (code "128") (name "unconnected-(U5B-PG10-Pad125)") (class "Default")
      (node (ref "U5") (pin "125") (pinfunction "PG10_125") (pintype "bidirectional+no_connect"))
    )
    (net (code "129") (name "unconnected-(U5B-PG11-Pad126)") (class "Default")
      (node (ref "U5") (pin "126") (pinfunction "PG11_126") (pintype "bidirectional+no_connect"))
    )
    (net (code "130") (name "unconnected-(U5B-PG12-Pad127)") (class "Default")
      (node (ref "U5") (pin "127") (pinfunction "PG12_127") (pintype "bidirectional+no_connect"))
    )
    (net (code "131") (name "unconnected-(U5B-PG13-Pad128)") (class "Default")
      (node (ref "U5") (pin "128") (pinfunction "PG13_128") (pintype "bidirectional+no_connect"))
    )
    (net (code "132") (name "unconnected-(U5B-PG14-Pad129)") (class "Default")
      (node (ref "U5") (pin "129") (pinfunction "PG14_129") (pintype "bidirectional+no_connect"))
    )
    (net (code "133") (name "unconnected-(U5B-PG15-Pad132)") (class "Default")
      (node (ref "U5") (pin "132") (pinfunction "PG15_132") (pintype "bidirectional+no_connect"))
    )
  )
)
